# TeensyAmp_R4_2.net
KiCad netlist of a schematic drawn in EAGLE
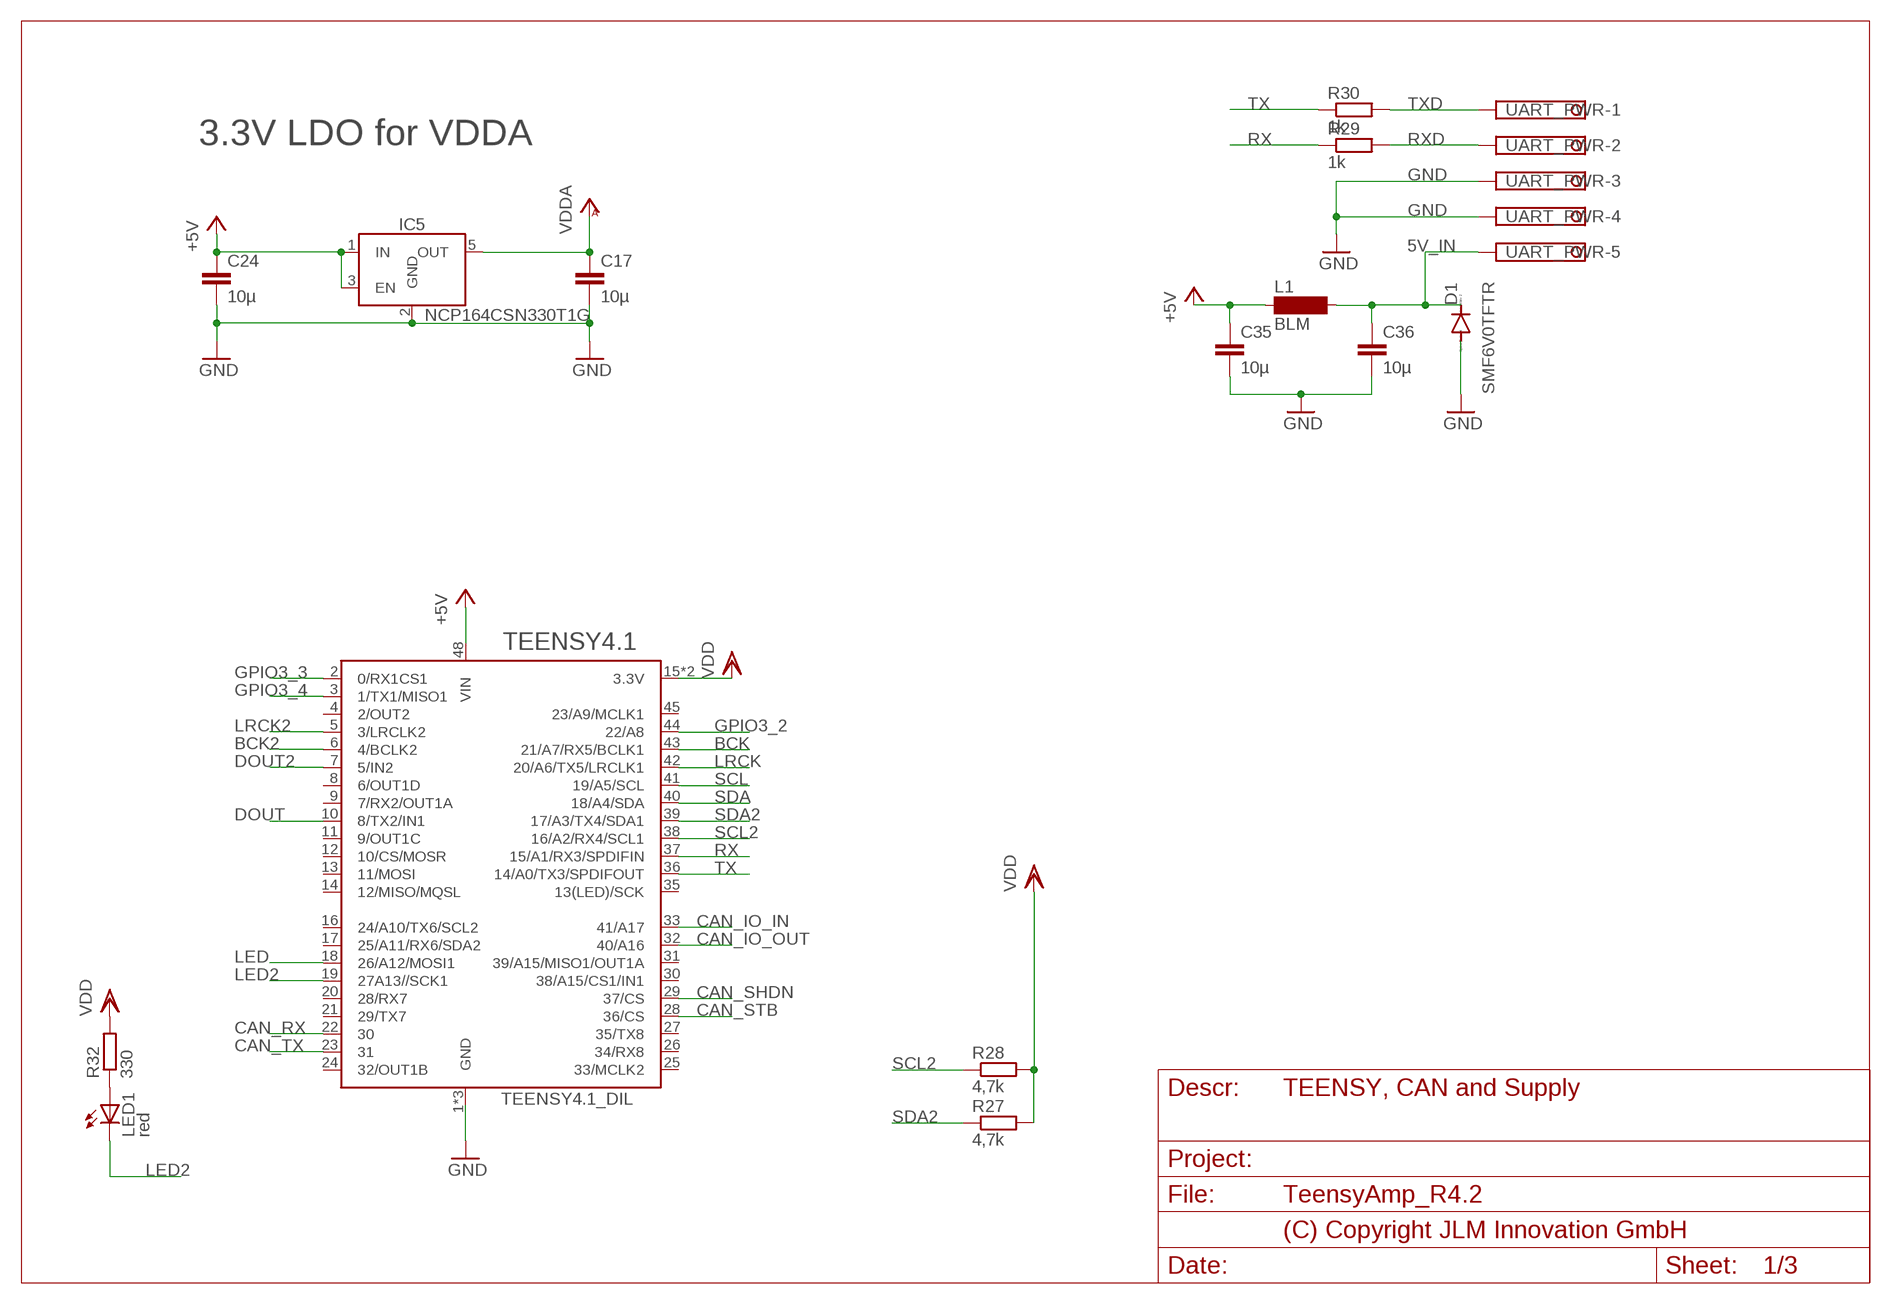
[diagram p0: schematic, sheet 1]
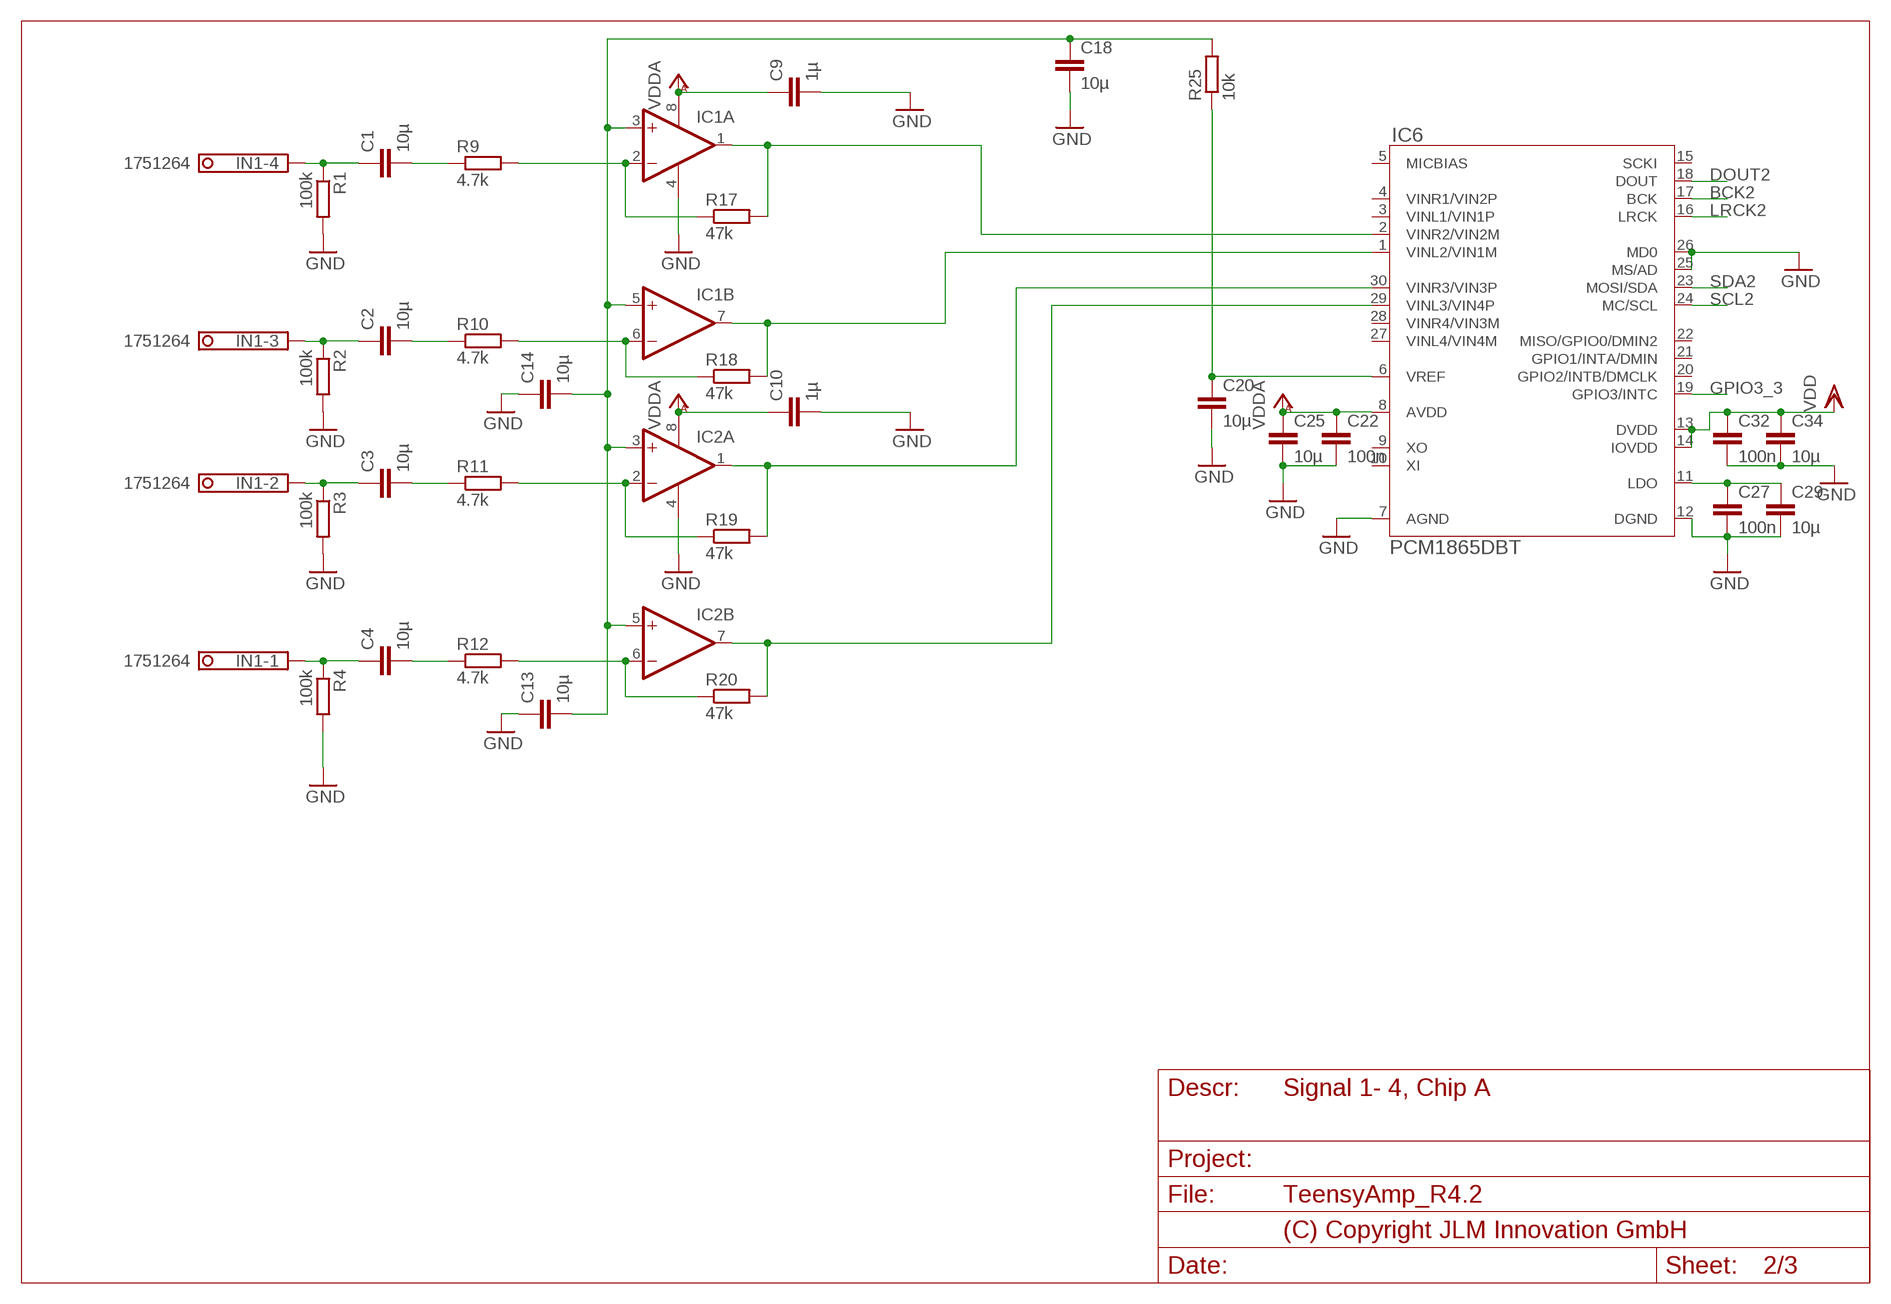
[diagram p1: schematic, sheet 2]
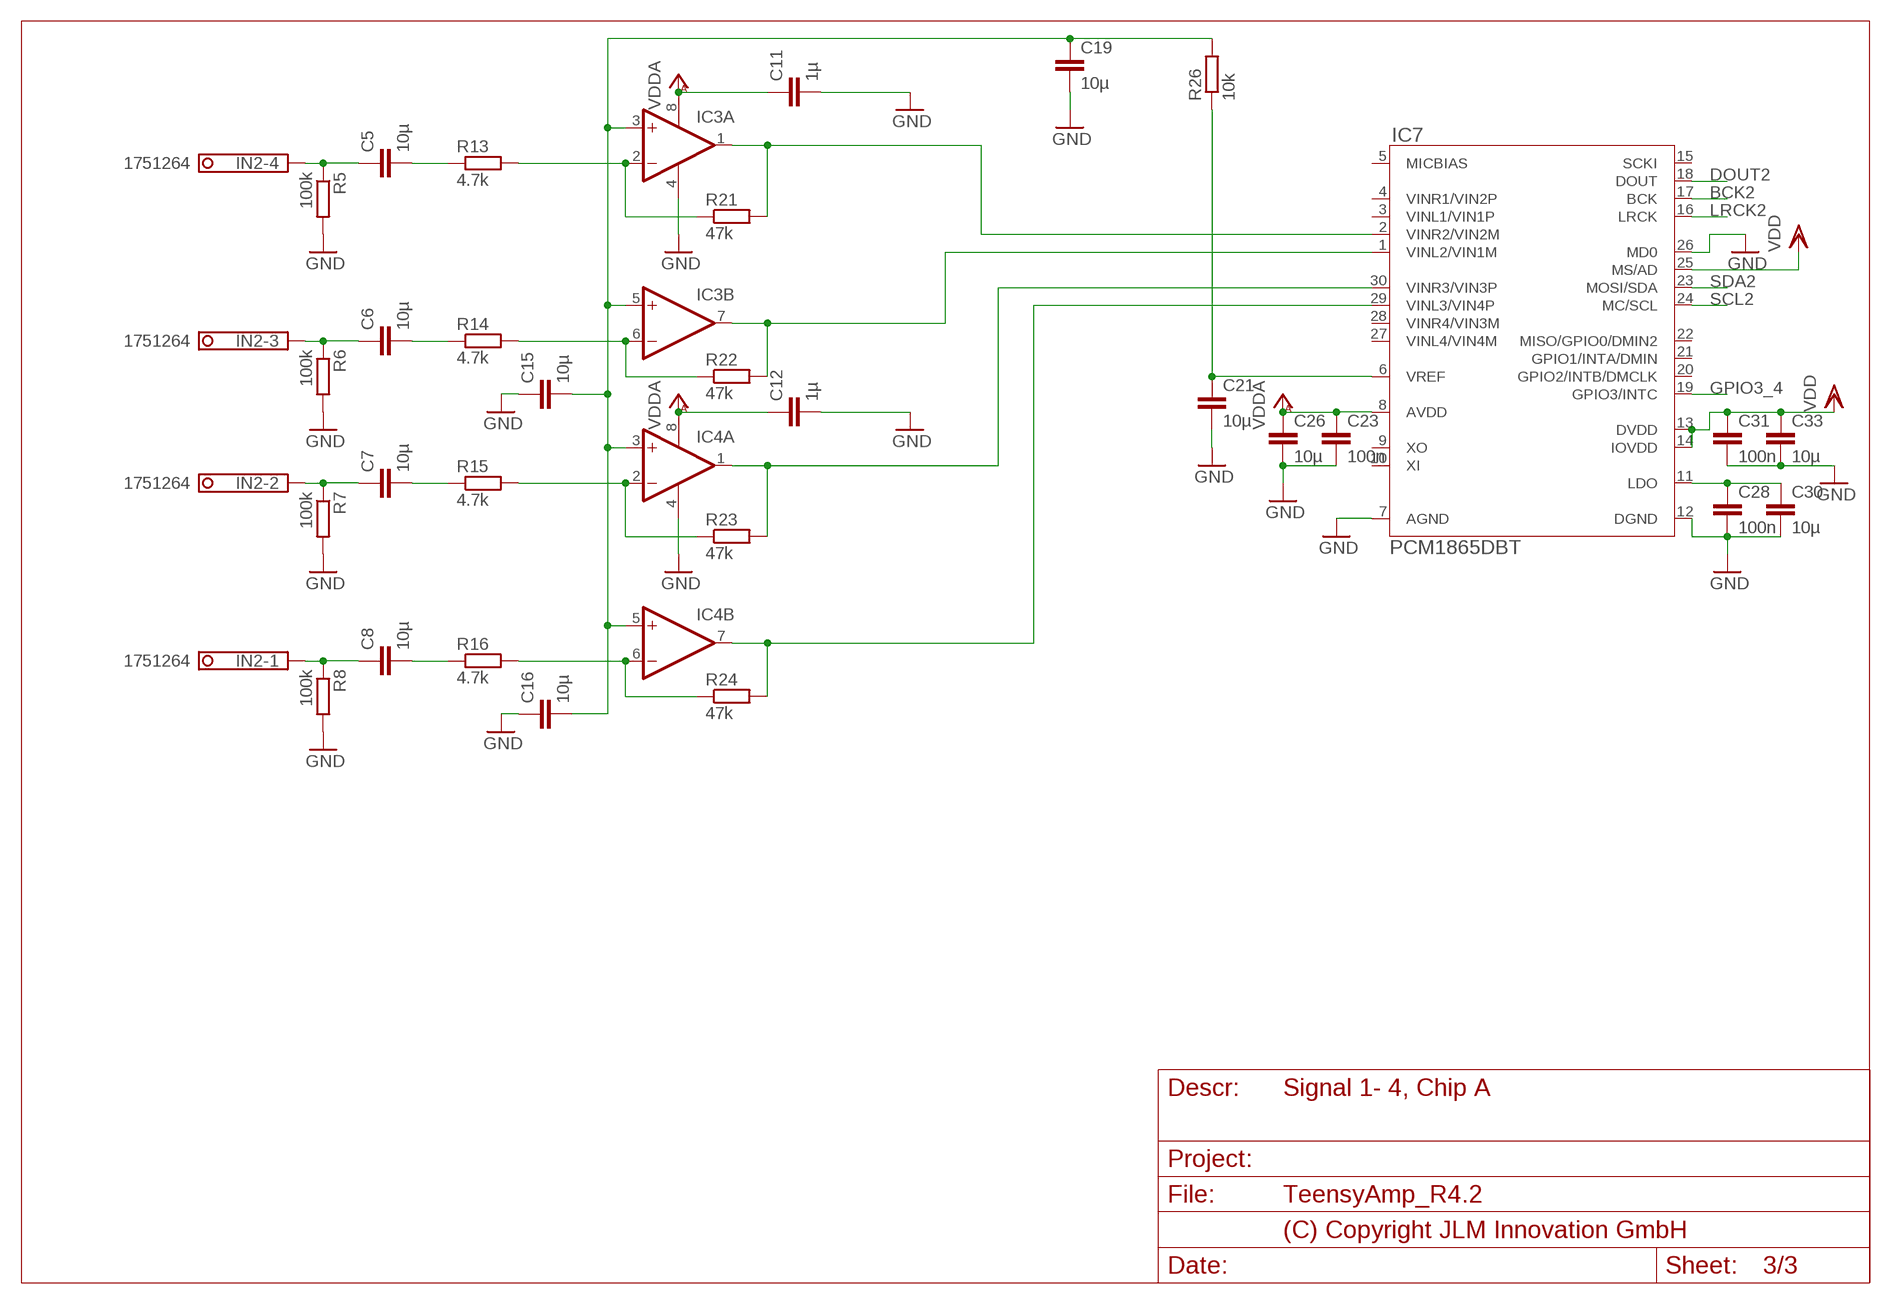
[diagram p2: schematic, sheet 3]

(export (version "E")
  (design (tool "Eeschema 10.0.6"))
  (components
    (comp (ref "C5")
      (value "10µ")
      (footprint "eagle-import:C0805")
      (libsource (lib "eagle-import") (part "C-EUC0805"))
    )
    (comp (ref "C6")
      (value "10µ")
      (footprint "eagle-import:C0805")
      (libsource (lib "eagle-import") (part "C-EUC0805"))
    )
    (comp (ref "C7")
      (value "10µ")
      (footprint "eagle-import:C0805")
      (libsource (lib "eagle-import") (part "C-EUC0805"))
    )
    (comp (ref "C8")
      (value "10µ")
      (footprint "eagle-import:C0805")
      (libsource (lib "eagle-import") (part "C-EUC0805"))
    )
    (comp (ref "C11")
      (value "1µ")
      (footprint "eagle-import:C0603")
      (libsource (lib "eagle-import") (part "C-EUC0603"))
    )
    (comp (ref "C12")
      (value "1µ")
      (footprint "eagle-import:C0603")
      (libsource (lib "eagle-import") (part "C-EUC0603"))
    )
    (comp (ref "C15")
      (value "10µ")
      (footprint "eagle-import:C0603")
      (libsource (lib "eagle-import") (part "C-EUC0603"))
    )
    (comp (ref "C16")
      (value "10µ")
      (footprint "eagle-import:C0603")
      (libsource (lib "eagle-import") (part "C-EUC0603"))
    )
    (comp (ref "C19")
      (value "10µ")
      (footprint "eagle-import:C0603")
      (libsource (lib "eagle-import") (part "C-EUC0603"))
    )
    (comp (ref "C21")
      (value "10µ")
      (footprint "eagle-import:C0603")
      (libsource (lib "eagle-import") (part "C-EUC0603"))
    )
    (comp (ref "C23")
      (value "100n")
      (footprint "eagle-import:C0603")
      (libsource (lib "eagle-import") (part "C-EUC0603"))
    )
    (comp (ref "C26")
      (value "10µ")
      (footprint "eagle-import:C0603")
      (libsource (lib "eagle-import") (part "C-EUC0603"))
    )
    (comp (ref "C28")
      (value "100n")
      (footprint "eagle-import:C0603")
      (libsource (lib "eagle-import") (part "C-EUC0603"))
    )
    (comp (ref "C30")
      (value "10µ")
      (footprint "eagle-import:C0603")
      (libsource (lib "eagle-import") (part "C-EUC0603"))
    )
    (comp (ref "C31")
      (value "100n")
      (footprint "eagle-import:C0603")
      (libsource (lib "eagle-import") (part "C-EUC0603"))
    )
    (comp (ref "C33")
      (value "10µ")
      (footprint "eagle-import:C0603")
      (libsource (lib "eagle-import") (part "C-EUC0603"))
    )
    (comp (ref "IC3")
      (value "OPA2344E")
      (footprint "eagle-import:MSOP08")
      (libsource (lib "eagle-import") (part "OPA2E344"))
    )
    (comp (ref "IC4")
      (value "OPA2344E")
      (footprint "eagle-import:MSOP08")
      (libsource (lib "eagle-import") (part "OPA2E344"))
    )
    (comp (ref "IC7")
      (value "PCM1865DBT")
      (footprint "eagle-import:SOP50P640X120-30N")
      (libsource (lib "eagle-import") (part "PCM1865DBT"))
    )
    (comp (ref "IN2")
      (value "1751264")
      (footprint "eagle-import:1751264")
      (fields (field (name "OC_FARNELL") "2478588") (field (name "OC_RS") "8024852"))
      (libsource (lib "eagle-import") (part "1751264"))
    )
    (comp (ref "R5")
      (value "100k")
      (footprint "eagle-import:R0603")
      (libsource (lib "eagle-import") (part "R_JLMR0603"))
    )
    (comp (ref "R6")
      (value "100k")
      (footprint "eagle-import:R0603")
      (libsource (lib "eagle-import") (part "R_JLMR0603"))
    )
    (comp (ref "R7")
      (value "100k")
      (footprint "eagle-import:R0603")
      (libsource (lib "eagle-import") (part "R_JLMR0603"))
    )
    (comp (ref "R8")
      (value "100k")
      (footprint "eagle-import:R0603")
      (libsource (lib "eagle-import") (part "R_JLMR0603"))
    )
    (comp (ref "R13")
      (value "4.7k")
      (footprint "eagle-import:R0603")
      (libsource (lib "eagle-import") (part "R_JLMR0603"))
    )
    (comp (ref "R14")
      (value "4.7k")
      (footprint "eagle-import:R0603")
      (libsource (lib "eagle-import") (part "R_JLMR0603"))
    )
    (comp (ref "R15")
      (value "4.7k")
      (footprint "eagle-import:R0603")
      (libsource (lib "eagle-import") (part "R_JLMR0603"))
    )
    (comp (ref "R16")
      (value "4.7k")
      (footprint "eagle-import:R0603")
      (libsource (lib "eagle-import") (part "R_JLMR0603"))
    )
    (comp (ref "R21")
      (value "47k")
      (footprint "eagle-import:R0603")
      (libsource (lib "eagle-import") (part "R_JLMR0603"))
    )
    (comp (ref "R22")
      (value "47k")
      (footprint "eagle-import:R0603")
      (libsource (lib "eagle-import") (part "R_JLMR0603"))
    )
    (comp (ref "R23")
      (value "47k")
      (footprint "eagle-import:R0603")
      (libsource (lib "eagle-import") (part "R_JLMR0603"))
    )
    (comp (ref "R24")
      (value "47k")
      (footprint "eagle-import:R0603")
      (libsource (lib "eagle-import") (part "R_JLMR0603"))
    )
    (comp (ref "R26")
      (value "10k")
      (footprint "eagle-import:R0603")
      (libsource (lib "eagle-import") (part "R_JLMR0603"))
    )
    (comp (ref "C17")
      (value "10µ")
      (footprint "eagle-import:C0603")
      (libsource (lib "eagle-import") (part "C-EUC0603"))
    )
    (comp (ref "C24")
      (value "10µ")
      (footprint "eagle-import:C0603")
      (libsource (lib "eagle-import") (part "C-EUC0603"))
    )
    (comp (ref "C35")
      (value "10µ")
      (footprint "eagle-import:C0805")
      (libsource (lib "eagle-import") (part "C-EUC0805"))
    )
    (comp (ref "C36")
      (value "10µ")
      (footprint "eagle-import:C0805")
      (libsource (lib "eagle-import") (part "C-EUC0805"))
    )
    (comp (ref "D1")
      (value "SMF6V0TFTR")
      (footprint "eagle-import:SOD123")
      (libsource (lib "eagle-import") (part "DIODE-SOD123"))
    )
    (comp (ref "IC5")
      (value "NCP164CSN330T1G")
      (footprint "eagle-import:SOT23-5")
      (libsource (lib "eagle-import") (part "LDO_ENSOT23-5"))
    )
    (comp (ref "L1")
      (value "BLM")
      (footprint "eagle-import:R0805")
      (libsource (lib "eagle-import") (part "L_JLM0805"))
    )
    (comp (ref "LED1")
      (value "red")
      (footprint "eagle-import:LED5MM")
      (libsource (lib "eagle-import") (part "LED5MM"))
    )
    (comp (ref "R27")
      (value "4,7k")
      (footprint "eagle-import:R0603")
      (libsource (lib "eagle-import") (part "R_JLMR0603"))
    )
    (comp (ref "R28")
      (value "4,7k")
      (footprint "eagle-import:R0603")
      (libsource (lib "eagle-import") (part "R_JLMR0603"))
    )
    (comp (ref "R29")
      (value "1k")
      (footprint "eagle-import:R0603")
      (libsource (lib "eagle-import") (part "R_JLMR0603"))
    )
    (comp (ref "R30")
      (value "1k")
      (footprint "eagle-import:R0603")
      (libsource (lib "eagle-import") (part "R_JLMR0603"))
    )
    (comp (ref "R32")
      (value "330")
      (footprint "eagle-import:R0603")
      (libsource (lib "eagle-import") (part "R_JLMR0603"))
    )
    (comp (ref "TEENSY4.1")
      (value "TEENSY4.1_DIL")
      (footprint "eagle-import:TEENSY4.1_DIL")
      (libsource (lib "eagle-import") (part "TEENSY4.1_DIL"))
    )
    (comp (ref "UART_PWR")
      (value "1751277")
      (footprint "eagle-import:1751277")
      (fields (field (name "OC_RS") "8024855"))
      (libsource (lib "eagle-import") (part "1751277"))
    )
    (comp (ref "C1")
      (value "10µ")
      (footprint "eagle-import:C0805")
      (libsource (lib "eagle-import") (part "C-EUC0805"))
    )
    (comp (ref "C2")
      (value "10µ")
      (footprint "eagle-import:C0805")
      (libsource (lib "eagle-import") (part "C-EUC0805"))
    )
    (comp (ref "C3")
      (value "10µ")
      (footprint "eagle-import:C0805")
      (libsource (lib "eagle-import") (part "C-EUC0805"))
    )
    (comp (ref "C4")
      (value "10µ")
      (footprint "eagle-import:C0805")
      (libsource (lib "eagle-import") (part "C-EUC0805"))
    )
    (comp (ref "C9")
      (value "1µ")
      (footprint "eagle-import:C0603")
      (libsource (lib "eagle-import") (part "C-EUC0603"))
    )
    (comp (ref "C10")
      (value "1µ")
      (footprint "eagle-import:C0603")
      (libsource (lib "eagle-import") (part "C-EUC0603"))
    )
    (comp (ref "C13")
      (value "10µ")
      (footprint "eagle-import:C0603")
      (libsource (lib "eagle-import") (part "C-EUC0603"))
    )
    (comp (ref "C14")
      (value "10µ")
      (footprint "eagle-import:C0603")
      (libsource (lib "eagle-import") (part "C-EUC0603"))
    )
    (comp (ref "C18")
      (value "10µ")
      (footprint "eagle-import:C0603")
      (libsource (lib "eagle-import") (part "C-EUC0603"))
    )
    (comp (ref "C20")
      (value "10µ")
      (footprint "eagle-import:C0603")
      (libsource (lib "eagle-import") (part "C-EUC0603"))
    )
    (comp (ref "C22")
      (value "100n")
      (footprint "eagle-import:C0603")
      (libsource (lib "eagle-import") (part "C-EUC0603"))
    )
    (comp (ref "C25")
      (value "10µ")
      (footprint "eagle-import:C0603")
      (libsource (lib "eagle-import") (part "C-EUC0603"))
    )
    (comp (ref "C27")
      (value "100n")
      (footprint "eagle-import:C0603")
      (libsource (lib "eagle-import") (part "C-EUC0603"))
    )
    (comp (ref "C29")
      (value "10µ")
      (footprint "eagle-import:C0603")
      (libsource (lib "eagle-import") (part "C-EUC0603"))
    )
    (comp (ref "C32")
      (value "100n")
      (footprint "eagle-import:C0603")
      (libsource (lib "eagle-import") (part "C-EUC0603"))
    )
    (comp (ref "C34")
      (value "10µ")
      (footprint "eagle-import:C0603")
      (libsource (lib "eagle-import") (part "C-EUC0603"))
    )
    (comp (ref "IC1")
      (value "OPA2344E")
      (footprint "eagle-import:MSOP08")
      (libsource (lib "eagle-import") (part "OPA2E344"))
    )
    (comp (ref "IC2")
      (value "OPA2344E")
      (footprint "eagle-import:MSOP08")
      (libsource (lib "eagle-import") (part "OPA2E344"))
    )
    (comp (ref "IC6")
      (value "PCM1865DBT")
      (footprint "eagle-import:SOP50P640X120-30N")
      (libsource (lib "eagle-import") (part "PCM1865DBT"))
    )
    (comp (ref "IN1")
      (value "1751264")
      (footprint "eagle-import:1751264")
      (fields (field (name "OC_FARNELL") "2478588"))
      (libsource (lib "eagle-import") (part "1751264"))
    )
    (comp (ref "R1")
      (value "100k")
      (footprint "eagle-import:R0603")
      (libsource (lib "eagle-import") (part "R_JLMR0603"))
    )
    (comp (ref "R2")
      (value "100k")
      (footprint "eagle-import:R0603")
      (libsource (lib "eagle-import") (part "R_JLMR0603"))
    )
    (comp (ref "R3")
      (value "100k")
      (footprint "eagle-import:R0603")
      (libsource (lib "eagle-import") (part "R_JLMR0603"))
    )
    (comp (ref "R4")
      (value "100k")
      (footprint "eagle-import:R0603")
      (libsource (lib "eagle-import") (part "R_JLMR0603"))
    )
    (comp (ref "R9")
      (value "4.7k")
      (footprint "eagle-import:R0603")
      (libsource (lib "eagle-import") (part "R_JLMR0603"))
    )
    (comp (ref "R10")
      (value "4.7k")
      (footprint "eagle-import:R0603")
      (libsource (lib "eagle-import") (part "R_JLMR0603"))
    )
    (comp (ref "R11")
      (value "4.7k")
      (footprint "eagle-import:R0603")
      (libsource (lib "eagle-import") (part "R_JLMR0603"))
    )
    (comp (ref "R12")
      (value "4.7k")
      (footprint "eagle-import:R0603")
      (libsource (lib "eagle-import") (part "R_JLMR0603"))
    )
    (comp (ref "R17")
      (value "47k")
      (footprint "eagle-import:R0603")
      (libsource (lib "eagle-import") (part "R_JLMR0603"))
    )
    (comp (ref "R18")
      (value "47k")
      (footprint "eagle-import:R0603")
      (libsource (lib "eagle-import") (part "R_JLMR0603"))
    )
    (comp (ref "R19")
      (value "47k")
      (footprint "eagle-import:R0603")
      (libsource (lib "eagle-import") (part "R_JLMR0603"))
    )
    (comp (ref "R20")
      (value "47k")
      (footprint "eagle-import:R0603")
      (libsource (lib "eagle-import") (part "R_JLMR0603"))
    )
    (comp (ref "R25")
      (value "10k")
      (footprint "eagle-import:R0603")
      (libsource (lib "eagle-import") (part "R_JLMR0603"))
    )
  )
  (nets
    (net (code "1") (name "+5V") (class "Default")
      (node (ref "C24") (pin "1") (pinfunction "1_1") (pintype "passive"))
      (node (ref "C35") (pin "1") (pinfunction "1_1") (pintype "passive"))
      (node (ref "IC5") (pin "1") (pinfunction "IN_1") (pintype "input"))
      (node (ref "IC5") (pin "3") (pinfunction "EN_3") (pintype "input"))
      (node (ref "L1") (pin "1") (pinfunction "1_1") (pintype "passive"))
      (node (ref "TEENSY4.1") (pin "48") (pinfunction "VIN_48") (pintype "power_in"))
    )
    (net (code "2") (name "5V_IN") (class "Default")
      (node (ref "C36") (pin "1") (pinfunction "1_1") (pintype "passive"))
      (node (ref "D1") (pin "C") (pinfunction "C_C") (pintype "passive"))
      (node (ref "L1") (pin "2") (pinfunction "2_2") (pintype "passive"))
      (node (ref "UART_PWR") (pin "5") (pinfunction "K_5") (pintype "passive"))
    )
    (net (code "3") (name "BCK") (class "Default")
      (node (ref "TEENSY4.1") (pin "43") (pinfunction "21/A7/RX5/BCLK1_43") (pintype "bidirectional"))
    )
    (net (code "4") (name "BCK2") (class "Default")
      (node (ref "IC6") (pin "17") (pinfunction "BCK_17") (pintype "bidirectional"))
      (node (ref "IC7") (pin "17") (pinfunction "BCK_17") (pintype "bidirectional"))
      (node (ref "TEENSY4.1") (pin "6") (pinfunction "4/BCLK2_6") (pintype "bidirectional"))
    )
    (net (code "5") (name "CAN_IO_IN") (class "Default")
      (node (ref "TEENSY4.1") (pin "33") (pinfunction "41/A17_33") (pintype "bidirectional"))
    )
    (net (code "6") (name "CAN_IO_OUT") (class "Default")
      (node (ref "TEENSY4.1") (pin "32") (pinfunction "40/A16_32") (pintype "bidirectional"))
    )
    (net (code "7") (name "CAN_RX") (class "Default")
      (node (ref "TEENSY4.1") (pin "22") (pinfunction "30_22") (pintype "bidirectional"))
    )
    (net (code "8") (name "CAN_SHDN") (class "Default")
      (node (ref "TEENSY4.1") (pin "29") (pinfunction "37/CS_29") (pintype "bidirectional"))
    )
    (net (code "9") (name "CAN_STB") (class "Default")
      (node (ref "TEENSY4.1") (pin "28") (pinfunction "36/CS_28") (pintype "bidirectional"))
    )
    (net (code "10") (name "CAN_TX") (class "Default")
      (node (ref "TEENSY4.1") (pin "23") (pinfunction "31_23") (pintype "bidirectional"))
    )
    (net (code "11") (name "DOUT") (class "Default")
      (node (ref "TEENSY4.1") (pin "10") (pinfunction "8/TX2/IN1_10") (pintype "bidirectional"))
    )
    (net (code "12") (name "DOUT2") (class "Default")
      (node (ref "IC6") (pin "18") (pinfunction "DOUT_18") (pintype "output"))
      (node (ref "IC7") (pin "18") (pinfunction "DOUT_18") (pintype "output"))
      (node (ref "TEENSY4.1") (pin "7") (pinfunction "5/IN2_7") (pintype "bidirectional"))
    )
    (net (code "13") (name "GND") (class "Default")
      (node (ref "C10") (pin "2") (pinfunction "2_2") (pintype "passive"))
      (node (ref "C11") (pin "2") (pinfunction "2_2") (pintype "passive"))
      (node (ref "C12") (pin "2") (pinfunction "2_2") (pintype "passive"))
      (node (ref "C13") (pin "1") (pinfunction "1_1") (pintype "passive"))
      (node (ref "C14") (pin "1") (pinfunction "1_1") (pintype "passive"))
      (node (ref "C15") (pin "1") (pinfunction "1_1") (pintype "passive"))
      (node (ref "C16") (pin "1") (pinfunction "1_1") (pintype "passive"))
      (node (ref "C17") (pin "2") (pinfunction "2_2") (pintype "passive"))
      (node (ref "C18") (pin "2") (pinfunction "2_2") (pintype "passive"))
      (node (ref "C19") (pin "2") (pinfunction "2_2") (pintype "passive"))
      (node (ref "C20") (pin "2") (pinfunction "2_2") (pintype "passive"))
      (node (ref "C21") (pin "2") (pinfunction "2_2") (pintype "passive"))
      (node (ref "C22") (pin "2") (pinfunction "2_2") (pintype "passive"))
      (node (ref "C23") (pin "2") (pinfunction "2_2") (pintype "passive"))
      (node (ref "C24") (pin "2") (pinfunction "2_2") (pintype "passive"))
      (node (ref "C25") (pin "2") (pinfunction "2_2") (pintype "passive"))
      (node (ref "C26") (pin "2") (pinfunction "2_2") (pintype "passive"))
      (node (ref "C27") (pin "2") (pinfunction "2_2") (pintype "passive"))
      (node (ref "C28") (pin "2") (pinfunction "2_2") (pintype "passive"))
      (node (ref "C29") (pin "2") (pinfunction "2_2") (pintype "passive"))
      (node (ref "C30") (pin "2") (pinfunction "2_2") (pintype "passive"))
      (node (ref "C31") (pin "2") (pinfunction "2_2") (pintype "passive"))
      (node (ref "C32") (pin "2") (pinfunction "2_2") (pintype "passive"))
      (node (ref "C33") (pin "2") (pinfunction "2_2") (pintype "passive"))
      (node (ref "C34") (pin "2") (pinfunction "2_2") (pintype "passive"))
      (node (ref "C35") (pin "2") (pinfunction "2_2") (pintype "passive"))
      (node (ref "C36") (pin "2") (pinfunction "2_2") (pintype "passive"))
      (node (ref "C9") (pin "2") (pinfunction "2_2") (pintype "passive"))
      (node (ref "D1") (pin "A") (pinfunction "A_A") (pintype "passive"))
      (node (ref "IC1") (pin "4") (pinfunction "V-_4") (pintype "power_in"))
      (node (ref "IC2") (pin "4") (pinfunction "V-_4") (pintype "power_in"))
      (node (ref "IC3") (pin "4") (pinfunction "V-_4") (pintype "power_in"))
      (node (ref "IC4") (pin "4") (pinfunction "V-_4") (pintype "power_in"))
      (node (ref "IC5") (pin "2") (pinfunction "GND_2") (pintype "power_in"))
      (node (ref "IC6") (pin "12") (pinfunction "DGND_12") (pintype "power_in"))
      (node (ref "IC6") (pin "25") (pinfunction "MS/AD_25") (pintype "input"))
      (node (ref "IC6") (pin "26") (pinfunction "MD0_26") (pintype "input"))
      (node (ref "IC6") (pin "7") (pinfunction "AGND_7") (pintype "power_in"))
      (node (ref "IC7") (pin "12") (pinfunction "DGND_12") (pintype "power_in"))
      (node (ref "IC7") (pin "26") (pinfunction "MD0_26") (pintype "input"))
      (node (ref "IC7") (pin "7") (pinfunction "AGND_7") (pintype "power_in"))
      (node (ref "R1") (pin "2") (pinfunction "2_2") (pintype "passive"))
      (node (ref "R2") (pin "2") (pinfunction "2_2") (pintype "passive"))
      (node (ref "R3") (pin "2") (pinfunction "2_2") (pintype "passive"))
      (node (ref "R4") (pin "2") (pinfunction "2_2") (pintype "passive"))
      (node (ref "R5") (pin "2") (pinfunction "2_2") (pintype "passive"))
      (node (ref "R6") (pin "2") (pinfunction "2_2") (pintype "passive"))
      (node (ref "R7") (pin "2") (pinfunction "2_2") (pintype "passive"))
      (node (ref "R8") (pin "2") (pinfunction "2_2") (pintype "passive"))
      (node (ref "TEENSY4.1") (pin "1") (pinfunction "GND_1") (pintype "power_in"))
      (node (ref "TEENSY4.1") (pin "34") (pinfunction "GND_34") (pintype "power_in"))
      (node (ref "TEENSY4.1") (pin "47") (pinfunction "GND_47") (pintype "power_in"))
      (node (ref "UART_PWR") (pin "3") (pinfunction "K_3") (pintype "passive"))
      (node (ref "UART_PWR") (pin "4") (pinfunction "K_4") (pintype "passive"))
    )
    (net (code "14") (name "GPIO3_2") (class "Default")
      (node (ref "TEENSY4.1") (pin "44") (pinfunction "22/A8_44") (pintype "bidirectional"))
    )
    (net (code "15") (name "GPIO3_3") (class "Default")
      (node (ref "IC6") (pin "19") (pinfunction "GPIO3/INTC_19") (pintype "bidirectional"))
      (node (ref "TEENSY4.1") (pin "2") (pinfunction "0/RX1CS1_2") (pintype "bidirectional"))
    )
    (net (code "16") (name "GPIO3_4") (class "Default")
      (node (ref "IC7") (pin "19") (pinfunction "GPIO3/INTC_19") (pintype "bidirectional"))
      (node (ref "TEENSY4.1") (pin "3") (pinfunction "1/TX1/MISO1_3") (pintype "bidirectional"))
    )
    (net (code "17") (name "LED") (class "Default")
      (node (ref "TEENSY4.1") (pin "18") (pinfunction "26/A12/MOSI1_18") (pintype "bidirectional"))
    )
    (net (code "18") (name "LED2") (class "Default")
      (node (ref "LED1") (pin "K") (pinfunction "C_K") (pintype "passive"))
      (node (ref "TEENSY4.1") (pin "19") (pinfunction "27A13//SCK1_19") (pintype "bidirectional"))
    )
    (net (code "19") (name "LRCK") (class "Default")
      (node (ref "TEENSY4.1") (pin "42") (pinfunction "20/A6/TX5/LRCLK1_42") (pintype "bidirectional"))
    )
    (net (code "20") (name "LRCK2") (class "Default")
      (node (ref "IC6") (pin "16") (pinfunction "LRCK_16") (pintype "bidirectional"))
      (node (ref "IC7") (pin "16") (pinfunction "LRCK_16") (pintype "bidirectional"))
      (node (ref "TEENSY4.1") (pin "5") (pinfunction "3/LRCLK2_5") (pintype "bidirectional"))
    )
    (net (code "21") (name "Net-(C1-Pad2)") (class "Default")
      (node (ref "C1") (pin "2") (pinfunction "2_2") (pintype "passive"))
      (node (ref "R9") (pin "1") (pinfunction "1_1") (pintype "passive"))
    )
    (net (code "22") (name "Net-(C2-Pad2)") (class "Default")
      (node (ref "C2") (pin "2") (pinfunction "2_2") (pintype "passive"))
      (node (ref "R10") (pin "1") (pinfunction "1_1") (pintype "passive"))
    )
    (net (code "23") (name "Net-(C3-Pad2)") (class "Default")
      (node (ref "C3") (pin "2") (pinfunction "2_2") (pintype "passive"))
      (node (ref "R11") (pin "1") (pinfunction "1_1") (pintype "passive"))
    )
    (net (code "24") (name "Net-(C4-Pad2)") (class "Default")
      (node (ref "C4") (pin "2") (pinfunction "2_2") (pintype "passive"))
      (node (ref "R12") (pin "1") (pinfunction "1_1") (pintype "passive"))
    )
    (net (code "25") (name "Net-(C5-Pad2)") (class "Default")
      (node (ref "C5") (pin "2") (pinfunction "2_2") (pintype "passive"))
      (node (ref "R13") (pin "1") (pinfunction "1_1") (pintype "passive"))
    )
    (net (code "26") (name "Net-(C6-Pad2)") (class "Default")
      (node (ref "C6") (pin "2") (pinfunction "2_2") (pintype "passive"))
      (node (ref "R14") (pin "1") (pinfunction "1_1") (pintype "passive"))
    )
    (net (code "27") (name "Net-(C7-Pad2)") (class "Default")
      (node (ref "C7") (pin "2") (pinfunction "2_2") (pintype "passive"))
      (node (ref "R15") (pin "1") (pinfunction "1_1") (pintype "passive"))
    )
    (net (code "28") (name "Net-(C8-Pad2)") (class "Default")
      (node (ref "C8") (pin "2") (pinfunction "2_2") (pintype "passive"))
      (node (ref "R16") (pin "1") (pinfunction "1_1") (pintype "passive"))
    )
    (net (code "29") (name "Net-(IC1A-+IN)") (class "Default")
      (node (ref "C13") (pin "2") (pinfunction "2_2") (pintype "passive"))
      (node (ref "C14") (pin "2") (pinfunction "2_2") (pintype "passive"))
      (node (ref "C18") (pin "1") (pinfunction "1_1") (pintype "passive"))
      (node (ref "IC1") (pin "3") (pinfunction "+IN_3") (pintype "input"))
      (node (ref "IC1") (pin "5") (pinfunction "+IN_5") (pintype "input"))
      (node (ref "IC2") (pin "3") (pinfunction "+IN_3") (pintype "input"))
      (node (ref "IC2") (pin "5") (pinfunction "+IN_5") (pintype "input"))
      (node (ref "R25") (pin "2") (pinfunction "2_2") (pintype "passive"))
    )
    (net (code "30") (name "Net-(IC1A--IN)") (class "Default")
      (node (ref "IC1") (pin "2") (pinfunction "-IN_2") (pintype "input"))
      (node (ref "R17") (pin "1") (pinfunction "1_1") (pintype "passive"))
      (node (ref "R9") (pin "2") (pinfunction "2_2") (pintype "passive"))
    )
    (net (code "31") (name "Net-(IC1A-OUT)") (class "Default")
      (node (ref "IC1") (pin "1") (pinfunction "OUT_1") (pintype "output"))
      (node (ref "IC6") (pin "2") (pinfunction "VINR2/VIN2M_2") (pintype "input"))
      (node (ref "R17") (pin "2") (pinfunction "2_2") (pintype "passive"))
    )
    (net (code "32") (name "Net-(IC1B--IN)") (class "Default")
      (node (ref "IC1") (pin "6") (pinfunction "-IN_6") (pintype "input"))
      (node (ref "R10") (pin "2") (pinfunction "2_2") (pintype "passive"))
      (node (ref "R18") (pin "1") (pinfunction "1_1") (pintype "passive"))
    )
    (net (code "33") (name "Net-(IC1B-OUT)") (class "Default")
      (node (ref "IC1") (pin "7") (pinfunction "OUT_7") (pintype "output"))
      (node (ref "IC6") (pin "1") (pinfunction "VINL2/VIN1M_1") (pintype "input"))
      (node (ref "R18") (pin "2") (pinfunction "2_2") (pintype "passive"))
    )
    (net (code "34") (name "Net-(IC2A--IN)") (class "Default")
      (node (ref "IC2") (pin "2") (pinfunction "-IN_2") (pintype "input"))
      (node (ref "R11") (pin "2") (pinfunction "2_2") (pintype "passive"))
      (node (ref "R19") (pin "1") (pinfunction "1_1") (pintype "passive"))
    )
    (net (code "35") (name "Net-(IC2A-OUT)") (class "Default")
      (node (ref "IC2") (pin "1") (pinfunction "OUT_1") (pintype "output"))
      (node (ref "IC6") (pin "30") (pinfunction "VINR3/VIN3P_30") (pintype "input"))
      (node (ref "R19") (pin "2") (pinfunction "2_2") (pintype "passive"))
    )
    (net (code "36") (name "Net-(IC2B--IN)") (class "Default")
      (node (ref "IC2") (pin "6") (pinfunction "-IN_6") (pintype "input"))
      (node (ref "R12") (pin "2") (pinfunction "2_2") (pintype "passive"))
      (node (ref "R20") (pin "1") (pinfunction "1_1") (pintype "passive"))
    )
    (net (code "37") (name "Net-(IC2B-OUT)") (class "Default")
      (node (ref "IC2") (pin "7") (pinfunction "OUT_7") (pintype "output"))
      (node (ref "IC6") (pin "29") (pinfunction "VINL3/VIN4P_29") (pintype "input"))
      (node (ref "R20") (pin "2") (pinfunction "2_2") (pintype "passive"))
    )
    (net (code "38") (name "Net-(IC3A-+IN)") (class "Default")
      (node (ref "C15") (pin "2") (pinfunction "2_2") (pintype "passive"))
      (node (ref "C16") (pin "2") (pinfunction "2_2") (pintype "passive"))
      (node (ref "C19") (pin "1") (pinfunction "1_1") (pintype "passive"))
      (node (ref "IC3") (pin "3") (pinfunction "+IN_3") (pintype "input"))
      (node (ref "IC3") (pin "5") (pinfunction "+IN_5") (pintype "input"))
      (node (ref "IC4") (pin "3") (pinfunction "+IN_3") (pintype "input"))
      (node (ref "IC4") (pin "5") (pinfunction "+IN_5") (pintype "input"))
      (node (ref "R26") (pin "2") (pinfunction "2_2") (pintype "passive"))
    )
    (net (code "39") (name "Net-(IC3A--IN)") (class "Default")
      (node (ref "IC3") (pin "2") (pinfunction "-IN_2") (pintype "input"))
      (node (ref "R13") (pin "2") (pinfunction "2_2") (pintype "passive"))
      (node (ref "R21") (pin "1") (pinfunction "1_1") (pintype "passive"))
    )
    (net (code "40") (name "Net-(IC3A-OUT)") (class "Default")
      (node (ref "IC3") (pin "1") (pinfunction "OUT_1") (pintype "output"))
      (node (ref "IC7") (pin "2") (pinfunction "VINR2/VIN2M_2") (pintype "input"))
      (node (ref "R21") (pin "2") (pinfunction "2_2") (pintype "passive"))
    )
    (net (code "41") (name "Net-(IC3B--IN)") (class "Default")
      (node (ref "IC3") (pin "6") (pinfunction "-IN_6") (pintype "input"))
      (node (ref "R14") (pin "2") (pinfunction "2_2") (pintype "passive"))
      (node (ref "R22") (pin "1") (pinfunction "1_1") (pintype "passive"))
    )
    (net (code "42") (name "Net-(IC3B-OUT)") (class "Default")
      (node (ref "IC3") (pin "7") (pinfunction "OUT_7") (pintype "output"))
      (node (ref "IC7") (pin "1") (pinfunction "VINL2/VIN1M_1") (pintype "input"))
      (node (ref "R22") (pin "2") (pinfunction "2_2") (pintype "passive"))
    )
    (net (code "43") (name "Net-(IC4A--IN)") (class "Default")
      (node (ref "IC4") (pin "2") (pinfunction "-IN_2") (pintype "input"))
      (node (ref "R15") (pin "2") (pinfunction "2_2") (pintype "passive"))
      (node (ref "R23") (pin "1") (pinfunction "1_1") (pintype "passive"))
    )
    (net (code "44") (name "Net-(IC4A-OUT)") (class "Default")
      (node (ref "IC4") (pin "1") (pinfunction "OUT_1") (pintype "output"))
      (node (ref "IC7") (pin "30") (pinfunction "VINR3/VIN3P_30") (pintype "input"))
      (node (ref "R23") (pin "2") (pinfunction "2_2") (pintype "passive"))
    )
    (net (code "45") (name "Net-(IC4B--IN)") (class "Default")
      (node (ref "IC4") (pin "6") (pinfunction "-IN_6") (pintype "input"))
      (node (ref "R16") (pin "2") (pinfunction "2_2") (pintype "passive"))
      (node (ref "R24") (pin "1") (pinfunction "1_1") (pintype "passive"))
    )
    (net (code "46") (name "Net-(IC4B-OUT)") (class "Default")
      (node (ref "IC4") (pin "7") (pinfunction "OUT_7") (pintype "output"))
      (node (ref "IC7") (pin "29") (pinfunction "VINL3/VIN4P_29") (pintype "input"))
      (node (ref "R24") (pin "2") (pinfunction "2_2") (pintype "passive"))
    )
    (net (code "47") (name "Net-(IC6-LDO)") (class "Default")
      (node (ref "C27") (pin "1") (pinfunction "1_1") (pintype "passive"))
      (node (ref "C29") (pin "1") (pinfunction "1_1") (pintype "passive"))
      (node (ref "IC6") (pin "11") (pinfunction "LDO_11") (pintype "bidirectional"))
    )
    (net (code "48") (name "Net-(IC6-VREF)") (class "Default")
      (node (ref "C20") (pin "1") (pinfunction "1_1") (pintype "passive"))
      (node (ref "IC6") (pin "6") (pinfunction "VREF_6") (pintype "output"))
      (node (ref "R25") (pin "1") (pinfunction "1_1") (pintype "passive"))
    )
    (net (code "49") (name "Net-(IC7-LDO)") (class "Default")
      (node (ref "C28") (pin "1") (pinfunction "1_1") (pintype "passive"))
      (node (ref "C30") (pin "1") (pinfunction "1_1") (pintype "passive"))
      (node (ref "IC7") (pin "11") (pinfunction "LDO_11") (pintype "bidirectional"))
    )
    (net (code "50") (name "Net-(IC7-VREF)") (class "Default")
      (node (ref "C21") (pin "1") (pinfunction "1_1") (pintype "passive"))
      (node (ref "IC7") (pin "6") (pinfunction "VREF_6") (pintype "output"))
      (node (ref "R26") (pin "1") (pinfunction "1_1") (pintype "passive"))
    )
    (net (code "51") (name "Net-(IN1A-K)") (class "Default")
      (node (ref "C4") (pin "1") (pinfunction "1_1") (pintype "passive"))
      (node (ref "IN1") (pin "1") (pinfunction "K_1") (pintype "passive"))
      (node (ref "R4") (pin "1") (pinfunction "1_1") (pintype "passive"))
    )
    (net (code "52") (name "Net-(IN1B-K)") (class "Default")
      (node (ref "C3") (pin "1") (pinfunction "1_1") (pintype "passive"))
      (node (ref "IN1") (pin "2") (pinfunction "K_2") (pintype "passive"))
      (node (ref "R3") (pin "1") (pinfunction "1_1") (pintype "passive"))
    )
    (net (code "53") (name "Net-(IN1C-K)") (class "Default")
      (node (ref "C2") (pin "1") (pinfunction "1_1") (pintype "passive"))
      (node (ref "IN1") (pin "3") (pinfunction "K_3") (pintype "passive"))
      (node (ref "R2") (pin "1") (pinfunction "1_1") (pintype "passive"))
    )
    (net (code "54") (name "Net-(IN1D-K)") (class "Default")
      (node (ref "C1") (pin "1") (pinfunction "1_1") (pintype "passive"))
      (node (ref "IN1") (pin "4") (pinfunction "K_4") (pintype "passive"))
      (node (ref "R1") (pin "1") (pinfunction "1_1") (pintype "passive"))
    )
    (net (code "55") (name "Net-(IN2A-K)") (class "Default")
      (node (ref "C8") (pin "1") (pinfunction "1_1") (pintype "passive"))
      (node (ref "IN2") (pin "1") (pinfunction "K_1") (pintype "passive"))
      (node (ref "R8") (pin "1") (pinfunction "1_1") (pintype "passive"))
    )
    (net (code "56") (name "Net-(IN2B-K)") (class "Default")
      (node (ref "C7") (pin "1") (pinfunction "1_1") (pintype "passive"))
      (node (ref "IN2") (pin "2") (pinfunction "K_2") (pintype "passive"))
      (node (ref "R7") (pin "1") (pinfunction "1_1") (pintype "passive"))
    )
    (net (code "57") (name "Net-(IN2C-K)") (class "Default")
      (node (ref "C6") (pin "1") (pinfunction "1_1") (pintype "passive"))
      (node (ref "IN2") (pin "3") (pinfunction "K_3") (pintype "passive"))
      (node (ref "R6") (pin "1") (pinfunction "1_1") (pintype "passive"))
    )
    (net (code "58") (name "Net-(IN2D-K)") (class "Default")
      (node (ref "C5") (pin "1") (pinfunction "1_1") (pintype "passive"))
      (node (ref "IN2") (pin "4") (pinfunction "K_4") (pintype "passive"))
      (node (ref "R5") (pin "1") (pinfunction "1_1") (pintype "passive"))
    )
    (net (code "59") (name "Net-(LED1-PadA)") (class "Default")
      (node (ref "LED1") (pin "A") (pinfunction "A_A") (pintype "passive"))
      (node (ref "R32") (pin "1") (pinfunction "1_1") (pintype "passive"))
    )
    (net (code "60") (name "RX") (class "Default")
      (node (ref "R29") (pin "1") (pinfunction "1_1") (pintype "passive"))
      (node (ref "TEENSY4.1") (pin "37") (pinfunction "15/A1/RX3/SPDIFIN_37") (pintype "bidirectional"))
    )
    (net (code "61") (name "RXD") (class "Default")
      (node (ref "R29") (pin "2") (pinfunction "2_2") (pintype "passive"))
      (node (ref "UART_PWR") (pin "2") (pinfunction "K_2") (pintype "passive"))
    )
    (net (code "62") (name "SCL") (class "Default")
      (node (ref "TEENSY4.1") (pin "41") (pinfunction "19/A5/SCL_41") (pintype "bidirectional"))
    )
    (net (code "63") (name "SCL2") (class "Default")
      (node (ref "IC6") (pin "24") (pinfunction "MC/SCL_24") (pintype "input"))
      (node (ref "IC7") (pin "24") (pinfunction "MC/SCL_24") (pintype "input"))
      (node (ref "R28") (pin "1") (pinfunction "1_1") (pintype "passive"))
      (node (ref "TEENSY4.1") (pin "38") (pinfunction "16/A2/RX4/SCL1_38") (pintype "bidirectional"))
    )
    (net (code "64") (name "SDA") (class "Default")
      (node (ref "TEENSY4.1") (pin "40") (pinfunction "18/A4/SDA_40") (pintype "bidirectional"))
    )
    (net (code "65") (name "SDA2") (class "Default")
      (node (ref "IC6") (pin "23") (pinfunction "MOSI/SDA_23") (pintype "bidirectional"))
      (node (ref "IC7") (pin "23") (pinfunction "MOSI/SDA_23") (pintype "bidirectional"))
      (node (ref "R27") (pin "1") (pinfunction "1_1") (pintype "passive"))
      (node (ref "TEENSY4.1") (pin "39") (pinfunction "17/A3/TX4/SDA1_39") (pintype "bidirectional"))
    )
    (net (code "66") (name "TX") (class "Default")
      (node (ref "R30") (pin "1") (pinfunction "1_1") (pintype "passive"))
      (node (ref "TEENSY4.1") (pin "36") (pinfunction "14/A0/TX3/SPDIFOUT_36") (pintype "bidirectional"))
    )
    (net (code "67") (name "TXD") (class "Default")
      (node (ref "R30") (pin "2") (pinfunction "2_2") (pintype "passive"))
      (node (ref "UART_PWR") (pin "1") (pinfunction "K_1") (pintype "passive"))
    )
    (net (code "68") (name "VDD") (class "Default")
      (node (ref "C31") (pin "1") (pinfunction "1_1") (pintype "passive"))
      (node (ref "C32") (pin "1") (pinfunction "1_1") (pintype "passive"))
      (node (ref "C33") (pin "1") (pinfunction "1_1") (pintype "passive"))
      (node (ref "C34") (pin "1") (pinfunction "1_1") (pintype "passive"))
      (node (ref "IC6") (pin "13") (pinfunction "DVDD_13") (pintype "power_in"))
      (node (ref "IC6") (pin "14") (pinfunction "IOVDD_14") (pintype "power_in"))
      (node (ref "IC7") (pin "13") (pinfunction "DVDD_13") (pintype "power_in"))
      (node (ref "IC7") (pin "14") (pinfunction "IOVDD_14") (pintype "power_in"))
      (node (ref "IC7") (pin "25") (pinfunction "MS/AD_25") (pintype "input"))
      (node (ref "R27") (pin "2") (pinfunction "2_2") (pintype "passive"))
      (node (ref "R28") (pin "2") (pinfunction "2_2") (pintype "passive"))
      (node (ref "R32") (pin "2") (pinfunction "2_2") (pintype "passive"))
      (node (ref "TEENSY4.1") (pin "15") (pinfunction "3.3V_15") (pintype "output"))
      (node (ref "TEENSY4.1") (pin "46") (pinfunction "3.3V_46") (pintype "output"))
    )
    (net (code "69") (name "VDDA") (class "Default")
      (node (ref "C10") (pin "1") (pinfunction "1_1") (pintype "passive"))
      (node (ref "C11") (pin "1") (pinfunction "1_1") (pintype "passive"))
      (node (ref "C12") (pin "1") (pinfunction "1_1") (pintype "passive"))
      (node (ref "C17") (pin "1") (pinfunction "1_1") (pintype "passive"))
      (node (ref "C22") (pin "1") (pinfunction "1_1") (pintype "passive"))
      (node (ref "C23") (pin "1") (pinfunction "1_1") (pintype "passive"))
      (node (ref "C25") (pin "1") (pinfunction "1_1") (pintype "passive"))
      (node (ref "C26") (pin "1") (pinfunction "1_1") (pintype "passive"))
      (node (ref "C9") (pin "1") (pinfunction "1_1") (pintype "passive"))
      (node (ref "IC1") (pin "8") (pinfunction "V+_8") (pintype "power_in"))
      (node (ref "IC2") (pin "8") (pinfunction "V+_8") (pintype "power_in"))
      (node (ref "IC3") (pin "8") (pinfunction "V+_8") (pintype "power_in"))
      (node (ref "IC4") (pin "8") (pinfunction "V+_8") (pintype "power_in"))
      (node (ref "IC5") (pin "5") (pinfunction "OUT_5") (pintype "output"))
      (node (ref "IC6") (pin "8") (pinfunction "AVDD_8") (pintype "power_in"))
      (node (ref "IC7") (pin "8") (pinfunction "AVDD_8") (pintype "power_in"))
    )
    (net (code "70") (name "unconnected-(IC6-GPIO1{slash}INTA{slash}DMIN-Pad21)") (class "Default")
      (node (ref "IC6") (pin "21") (pinfunction "GPIO1/INTA/DMIN_21") (pintype "bidirectional"))
    )
    (net (code "71") (name "unconnected-(IC6-GPIO2{slash}INTB{slash}DMCLK-Pad20)") (class "Default")
      (node (ref "IC6") (pin "20") (pinfunction "GPIO2/INTB/DMCLK_20") (pintype "bidirectional"))
    )
    (net (code "72") (name "unconnected-(IC6-MICBIAS-Pad5)") (class "Default")
      (node (ref "IC6") (pin "5") (pinfunction "MICBIAS_5") (pintype "input"))
    )
    (net (code "73") (name "unconnected-(IC6-MISO{slash}GPIO0{slash}DMIN2-Pad22)") (class "Default")
      (node (ref "IC6") (pin "22") (pinfunction "MISO/GPIO0/DMIN2_22") (pintype "bidirectional"))
    )
    (net (code "74") (name "unconnected-(IC6-SCKI-Pad15)") (class "Default")
      (node (ref "IC6") (pin "15") (pinfunction "SCKI_15") (pintype "input"))
    )
    (net (code "75") (name "unconnected-(IC6-VINL1{slash}VIN1P-Pad3)") (class "Default")
      (node (ref "IC6") (pin "3") (pinfunction "VINL1/VIN1P_3") (pintype "input"))
    )
    (net (code "76") (name "unconnected-(IC6-VINL4{slash}VIN4M-Pad27)") (class "Default")
      (node (ref "IC6") (pin "27") (pinfunction "VINL4/VIN4M_27") (pintype "input"))
    )
    (net (code "77") (name "unconnected-(IC6-VINR1{slash}VIN2P-Pad4)") (class "Default")
      (node (ref "IC6") (pin "4") (pinfunction "VINR1/VIN2P_4") (pintype "input"))
    )
    (net (code "78") (name "unconnected-(IC6-VINR4{slash}VIN3M-Pad28)") (class "Default")
      (node (ref "IC6") (pin "28") (pinfunction "VINR4/VIN3M_28") (pintype "input"))
    )
    (net (code "79") (name "unconnected-(IC6-XI-Pad10)") (class "Default")
      (node (ref "IC6") (pin "10") (pinfunction "XI_10") (pintype "input"))
    )
    (net (code "80") (name "unconnected-(IC6-XO-Pad9)") (class "Default")
      (node (ref "IC6") (pin "9") (pinfunction "XO_9") (pintype "output"))
    )
    (net (code "81") (name "unconnected-(IC7-GPIO1{slash}INTA{slash}DMIN-Pad21)") (class "Default")
      (node (ref "IC7") (pin "21") (pinfunction "GPIO1/INTA/DMIN_21") (pintype "bidirectional"))
    )
    (net (code "82") (name "unconnected-(IC7-GPIO2{slash}INTB{slash}DMCLK-Pad20)") (class "Default")
      (node (ref "IC7") (pin "20") (pinfunction "GPIO2/INTB/DMCLK_20") (pintype "bidirectional"))
    )
    (net (code "83") (name "unconnected-(IC7-MICBIAS-Pad5)") (class "Default")
      (node (ref "IC7") (pin "5") (pinfunction "MICBIAS_5") (pintype "input"))
    )
    (net (code "84") (name "unconnected-(IC7-MISO{slash}GPIO0{slash}DMIN2-Pad22)") (class "Default")
      (node (ref "IC7") (pin "22") (pinfunction "MISO/GPIO0/DMIN2_22") (pintype "bidirectional"))
    )
    (net (code "85") (name "unconnected-(IC7-SCKI-Pad15)") (class "Default")
      (node (ref "IC7") (pin "15") (pinfunction "SCKI_15") (pintype "input"))
    )
    (net (code "86") (name "unconnected-(IC7-VINL1{slash}VIN1P-Pad3)") (class "Default")
      (node (ref "IC7") (pin "3") (pinfunction "VINL1/VIN1P_3") (pintype "input"))
    )
    (net (code "87") (name "unconnected-(IC7-VINL4{slash}VIN4M-Pad27)") (class "Default")
      (node (ref "IC7") (pin "27") (pinfunction "VINL4/VIN4M_27") (pintype "input"))
    )
    (net (code "88") (name "unconnected-(IC7-VINR1{slash}VIN2P-Pad4)") (class "Default")
      (node (ref "IC7") (pin "4") (pinfunction "VINR1/VIN2P_4") (pintype "input"))
    )
    (net (code "89") (name "unconnected-(IC7-VINR4{slash}VIN3M-Pad28)") (class "Default")
      (node (ref "IC7") (pin "28") (pinfunction "VINR4/VIN3M_28") (pintype "input"))
    )
    (net (code "90") (name "unconnected-(IC7-XI-Pad10)") (class "Default")
      (node (ref "IC7") (pin "10") (pinfunction "XI_10") (pintype "input"))
    )
    (net (code "91") (name "unconnected-(IC7-XO-Pad9)") (class "Default")
      (node (ref "IC7") (pin "9") (pinfunction "XO_9") (pintype "output"))
    )
    (net (code "92") (name "unconnected-(TEENSY4.1-2{slash}OUT2-Pad4)") (class "Default")
      (node (ref "TEENSY4.1") (pin "4") (pinfunction "2/OUT2_4") (pintype "bidirectional"))
    )
    (net (code "93") (name "unconnected-(TEENSY4.1-6{slash}OUT1D-Pad8)") (class "Default")
      (node (ref "TEENSY4.1") (pin "8") (pinfunction "6/OUT1D_8") (pintype "bidirectional"))
    )
    (net (code "94") (name "unconnected-(TEENSY4.1-7{slash}RX2{slash}OUT1A-Pad9)") (class "Default")
      (node (ref "TEENSY4.1") (pin "9") (pinfunction "7/RX2/OUT1A_9") (pintype "bidirectional"))
    )
    (net (code "95") (name "unconnected-(TEENSY4.1-9{slash}OUT1C-Pad11)") (class "Default")
      (node (ref "TEENSY4.1") (pin "11") (pinfunction "9/OUT1C_11") (pintype "bidirectional"))
    )
    (net (code "96") (name "unconnected-(TEENSY4.1-10{slash}CS{slash}MOSR-Pad12)") (class "Default")
      (node (ref "TEENSY4.1") (pin "12") (pinfunction "10/CS/MOSR_12") (pintype "bidirectional"))
    )
    (net (code "97") (name "unconnected-(TEENSY4.1-11{slash}MOSI-Pad13)") (class "Default")
      (node (ref "TEENSY4.1") (pin "13") (pinfunction "11/MOSI_13") (pintype "bidirectional"))
    )
    (net (code "98") (name "unconnected-(TEENSY4.1-12{slash}MISO{slash}MQSL-Pad14)") (class "Default")
      (node (ref "TEENSY4.1") (pin "14") (pinfunction "12/MISO/MQSL_14") (pintype "bidirectional"))
    )
    (net (code "99") (name "unconnected-(TEENSY4.1-13(LED){slash}SCK-Pad35)") (class "Default")
      (node (ref "TEENSY4.1") (pin "35") (pinfunction "13(LED)/SCK_35") (pintype "bidirectional"))
    )
    (net (code "100") (name "unconnected-(TEENSY4.1-23{slash}A9{slash}MCLK1-Pad45)") (class "Default")
      (node (ref "TEENSY4.1") (pin "45") (pinfunction "23/A9/MCLK1_45") (pintype "bidirectional"))
    )
    (net (code "101") (name "unconnected-(TEENSY4.1-24{slash}A10{slash}TX6{slash}SCL2-Pad16)") (class "Default")
      (node (ref "TEENSY4.1") (pin "16") (pinfunction "24/A10/TX6/SCL2_16") (pintype "bidirectional"))
    )
    (net (code "102") (name "unconnected-(TEENSY4.1-25{slash}A11{slash}RX6{slash}SDA2-Pad17)") (class "Default")
      (node (ref "TEENSY4.1") (pin "17") (pinfunction "25/A11/RX6/SDA2_17") (pintype "bidirectional"))
    )
    (net (code "103") (name "unconnected-(TEENSY4.1-28{slash}RX7-Pad20)") (class "Default")
      (node (ref "TEENSY4.1") (pin "20") (pinfunction "28/RX7_20") (pintype "bidirectional"))
    )
    (net (code "104") (name "unconnected-(TEENSY4.1-29{slash}TX7-Pad21)") (class "Default")
      (node (ref "TEENSY4.1") (pin "21") (pinfunction "29/TX7_21") (pintype "bidirectional"))
    )
    (net (code "105") (name "unconnected-(TEENSY4.1-32{slash}OUT1B-Pad24)") (class "Default")
      (node (ref "TEENSY4.1") (pin "24") (pinfunction "32/OUT1B_24") (pintype "bidirectional"))
    )
    (net (code "106") (name "unconnected-(TEENSY4.1-33{slash}MCLK2-Pad25)") (class "Default")
      (node (ref "TEENSY4.1") (pin "25") (pinfunction "33/MCLK2_25") (pintype "bidirectional"))
    )
    (net (code "107") (name "unconnected-(TEENSY4.1-34{slash}RX8-Pad26)") (class "Default")
      (node (ref "TEENSY4.1") (pin "26") (pinfunction "34/RX8_26") (pintype "bidirectional"))
    )
    (net (code "108") (name "unconnected-(TEENSY4.1-35{slash}TX8-Pad27)") (class "Default")
      (node (ref "TEENSY4.1") (pin "27") (pinfunction "35/TX8_27") (pintype "bidirectional"))
    )
    (net (code "109") (name "unconnected-(TEENSY4.1-38{slash}A15{slash}CS1{slash}IN1-Pad30)") (class "Default")
      (node (ref "TEENSY4.1") (pin "30") (pinfunction "38/A15/CS1/IN1_30") (pintype "bidirectional"))
    )
    (net (code "110") (name "unconnected-(TEENSY4.1-39{slash}A15{slash}MISO1{slash}OUT1A-Pad31)") (class "Default")
      (node (ref "TEENSY4.1") (pin "31") (pinfunction "39/A15/MISO1/OUT1A_31") (pintype "bidirectional"))
    )
  )
)
